# metal-detector.net
KiCad netlist of a schematic drawn in Altium Designer
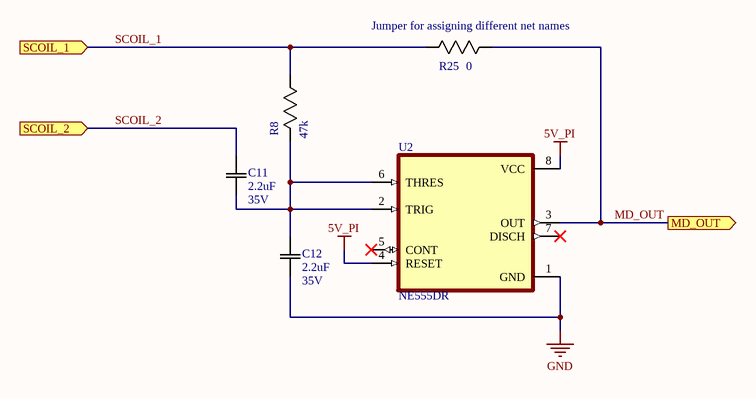
[diagram p0: metal-detector.SchDoc]

(export (version "E")
  (design (tool "Eeschema 10.0.6"))
  (components
    (comp (ref "C11")
      (value "2.2uF")
      (footprint "0805")
      (description "CAP CER 2.2UF 35V X7R 0603/0805")
      (fields
        (field (name "TOLERANCE") "10%")
        (field (name "RATING") "35V")
        (field (name "PART NUMBER") "CAP 2.2uF 35V")
      )
      (libsource (lib "capacitor_library") (part "CAP 2.2uF 35V"))
    )
    (comp (ref "C12")
      (value "2.2uF")
      (footprint "0805")
      (description "CAP CER 2.2UF 35V X7R 0603/0805")
      (fields
        (field (name "TOLERANCE") "10%")
        (field (name "RATING") "35V")
        (field (name "PART NUMBER") "CAP 2.2uF 35V")
      )
      (libsource (lib "capacitor_library") (part "CAP 2.2uF 35V"))
    )
    (comp (ref "R8")
      (value "47k")
      (footprint "0805")
      (description "RES SMD 47K OHM 1% 1/8W 0603")
      (fields (field (name "TOLERANCE") "1%") (field (name "PART NUMBER") "RES 47k 1/8W - 1%"))
      (libsource (lib "Resistor_Library") (part "RES 47k 1/8W - 1%"))
    )
    (comp (ref "R25")
      (value "0")
      (footprint "0805")
      (description "Default Resistor Symbol")
      (fields (field (name "PART NUMBER") "RES 0 JUMPER 0603"))
      (libsource (lib "Resistor_Library") (part "RES_DEFAULT"))
    )
    (comp (ref "U2")
      (value "NE555DR")
      (footprint "SOIC127P599X175-8N")
      (fields (field (name "MF") "{'manufacturer': u'Texas Instruments'}"))
      (libsource (lib "NE555DR") (part "NE555DR"))
    )
  )
  (nets
    (net (code "1") (name "/MD_OUT") (class "Default")
      (node (ref "R25") (pin "1") (pinfunction "R1_1") (pintype "passive"))
      (node (ref "U2") (pin "3") (pinfunction "OUT_3") (pintype "output"))
    )
    (net (code "2") (name "/SCOIL_1") (class "Default")
      (node (ref "R25") (pin "2") (pinfunction "R2_2") (pintype "passive"))
      (node (ref "R8") (pin "1") (pinfunction "R1_1") (pintype "passive"))
    )
    (net (code "3") (name "/SCOIL_2") (class "Default")
      (node (ref "C11") (pin "2") (pinfunction "C2_2") (pintype "passive"))
    )
    (net (code "4") (name "5V_PI") (class "Default")
      (node (ref "U2") (pin "4") (pinfunction "RESET_4") (pintype "input"))
      (node (ref "U2") (pin "8") (pinfunction "VCC_8") (pintype "power_in"))
    )
    (net (code "5") (name "GND") (class "Default")
      (node (ref "C12") (pin "1") (pinfunction "C1_1") (pintype "passive"))
      (node (ref "U2") (pin "1") (pinfunction "GND_1") (pintype "power_in"))
    )
    (net (code "6") (name "Net-(C11-C1)") (class "Default")
      (node (ref "C11") (pin "1") (pinfunction "C1_1") (pintype "passive"))
      (node (ref "C12") (pin "2") (pinfunction "C2_2") (pintype "passive"))
      (node (ref "R8") (pin "2") (pinfunction "R2_2") (pintype "passive"))
      (node (ref "U2") (pin "2") (pinfunction "TRIG_2") (pintype "input"))
      (node (ref "U2") (pin "6") (pinfunction "THRES_6") (pintype "input"))
    )
    (net (code "7") (name "unconnected-(U2-CONT-Pad5)") (class "Default")
      (node (ref "U2") (pin "5") (pinfunction "CONT_5") (pintype "bidirectional+no_connect"))
    )
    (net (code "8") (name "unconnected-(U2-DISCH-Pad7)") (class "Default")
      (node (ref "U2") (pin "7") (pinfunction "DISCH_7") (pintype "output+no_connect"))
    )
  )
)
